# PSU.net
KiCad netlist of a schematic drawn in Altium Designer
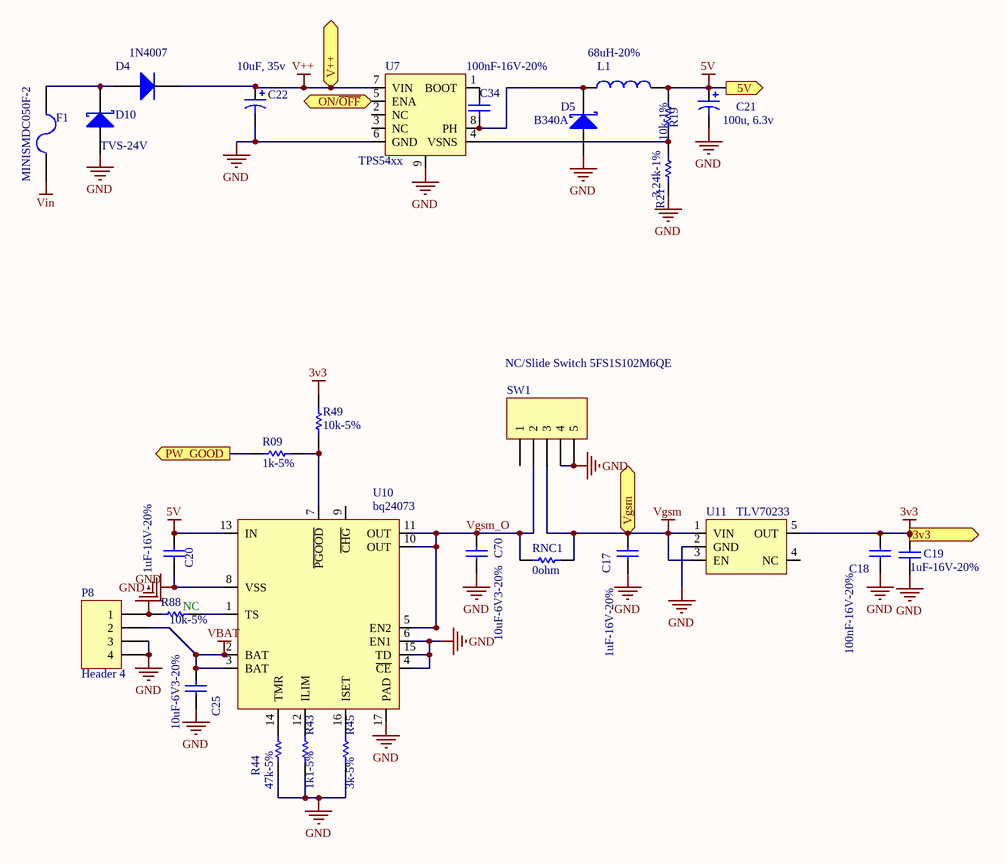
[diagram p0: PSU.SchDoc]

(export (version "E")
  (design (tool "Eeschema 10.0.6"))
  (components
    (comp (ref "C17")
      (value "1uF-16V-20%")
      (footprint "C0603")
      (description "CAP CER 1UF 16V Y5V 0603")
      (fields
        (field (name "MANUFACTURER") "Yageo")
        (field (name "DIGI-KEY PART NUMBER") "311-1372-1-ND")
        (field (name "PUBLISHER") "Altium Limited")
      )
      (libsource (lib "Miscellaneous Devices") (part "Cap"))
    )
    (comp (ref "C18")
      (value "100nF-16V-20%")
      (footprint "C0402")
      (description "CAP CER 0.1UF 16V Y5V 0402")
      (fields
        (field (name "MANUFACTURER") "Yageo")
        (field (name "DIGI-KEY PART NUMBER") "311-1047-1-ND")
        (field (name "PUBLISHER") "Altium Limited")
      )
      (libsource (lib "Miscellaneous Devices") (part "Cap"))
    )
    (comp (ref "C19")
      (value "1uF-16V-20%")
      (footprint "C0603")
      (description "CAP CER 1UF 16V Y5V 0603")
      (fields
        (field (name "MANUFACTURER") "Yageo")
        (field (name "DIGI-KEY PART NUMBER") "311-1372-1-ND")
        (field (name "PUBLISHER") "Altium Limited")
      )
      (libsource (lib "Miscellaneous Devices") (part "Cap"))
    )
    (comp (ref "C20")
      (value "1uF-16V-20%")
      (footprint "C0603")
      (description "CAP CER 1UF 16V Y5V 0603")
      (fields
        (field (name "MANUFACTURER") "Yageo")
        (field (name "DIGI-KEY PART NUMBER") "311-1372-1-ND")
        (field (name "PUBLISHER") "Altium Limited")
      )
      (libsource (lib "Miscellaneous Devices") (part "Cap"))
    )
    (comp (ref "C21")
      (value "100u, 6.3v")
      (footprint "CAPACITOR SIZE_C(D5.3)")
      (description "CAP ALUM 100UF 10V 20% SMD")
      (fields
        (field (name "DIGI-KEY PART NUMBER") "PCE3867TR-ND")
        (field (name "MANUFACTURER") "Panasonic Electronic Components")
        (field (name "PUBLISHER") "Altium Limited")
      )
      (libsource (lib "Miscellaneous Devices") (part "Cap Pol3"))
    )
    (comp (ref "C22")
      (value "10uF, 35v")
      (footprint "CAPACITOR SIZE_C(D5.3)")
      (description "CAP ALUM 10UF 35V 20% SMD")
      (fields
        (field (name "DIGI-KEY PART NUMBER") "PCE3947TR-ND")
        (field (name "MANUFACTURER") "Panasonic Electronic Components")
        (field (name "PUBLISHER") "Altium Limited")
      )
      (libsource (lib "Miscellaneous Devices") (part "Cap Pol3"))
    )
    (comp (ref "C25")
      (value "10uF-6V3-20%")
      (footprint "C0603")
      (description "CAP CER 10UF 6.3V 20% X5R 0603")
      (fields
        (field (name "MANUFACTURER") "Yageo")
        (field (name "DIGI-KEY PART NUMBER") "311-1448-1-ND")
        (field (name "PUBLISHER") "Altium Limited")
      )
      (libsource (lib "Miscellaneous Devices") (part "Cap"))
    )
    (comp (ref "C34")
      (value "100nF-16V-20%")
      (footprint "C0402")
      (description "CAP CER 0.1UF 16V Y5V 0402")
      (fields
        (field (name "MANUFACTURER") "Yageo")
        (field (name "DIGI-KEY PART NUMBER") "311-1047-1-ND")
        (field (name "PUBLISHER") "Altium Limited")
      )
      (libsource (lib "Miscellaneous Devices") (part "Cap"))
    )
    (comp (ref "C70")
      (value "10uF-6V3-20%")
      (footprint "C0603")
      (description "CAP CER 10UF 6.3V 20% X5R 0603")
      (fields
        (field (name "MANUFACTURER") "Yageo")
        (field (name "DIGI-KEY PART NUMBER") "311-1448-1-ND")
        (field (name "PUBLISHER") "Altium Limited")
      )
      (libsource (lib "Miscellaneous Devices") (part "Cap"))
    )
    (comp (ref "D4")
      (value "1N4007")
      (footprint "DO-214AC (SMA)")
      (description "DIODE GEN PURPOSE 1000V 1A SMA")
      (fields
        (field (name "DIGI-KEY PART NUMBER") "641-1018-1-ND")
        (field (name "MANUFACTURER PART NUMBER") "CGRA4007-G")
        (field (name "PUBLISHER") "Altium Limited")
      )
      (libsource (lib "Miscellaneous Devices") (part "Diode"))
    )
    (comp (ref "D5")
      (value "B340A")
      (footprint "DO-214AC (SMA)")
      (description "DIODE SCHOTTKY 40V 3A SMA")
      (fields
        (field (name "DIGI-KEY PART NUMBER") "B340A-E3/61TGITR-ND")
        (field (name "MANUFACTURER PART NUMBER") "B340A-E3/61T")
        (field (name "PUBLISHER") "Altium Limited")
      )
      (libsource (lib "Miscellaneous Devices") (part "D Schottky"))
    )
    (comp (ref "D10")
      (value "TVS-24V")
      (footprint "DO-214AB (SMC)")
      (description "DIODE TVS 24V 1500W UNI 5% SMC")
      (fields
        (field (name "DIGI-KEY PART NUMBER") "SMCJ24ALFTR-ND")
        (field (name "MANUFACTURER PART NUMBER") "SMCJ24A")
        (field (name "PUBLISHER") "Altium Limited")
      )
      (libsource (lib "Miscellaneous Devices") (part "D Schottky"))
    )
    (comp (ref "F1")
      (value "MINISMDC050F-2")
      (footprint "PTC1812")
      (description "POLYSWITCH .50A RESET FUSE SMD")
      (fields
        (field (name "DIGI-KEY PART NUMBER") "MINISMDC050FCT-ND")
        (field (name "MANUFACTURER") "TE Connectivity")
        (field (name "PUBLISHER") "Altium Limited")
      )
      (libsource (lib "Miscellaneous Devices") (part "Fuse 2"))
    )
    (comp (ref "L1")
      (value "68uH-20%")
      (footprint "68uH-1A")
      (description "INDUCTOR POWER 68UH SMD")
      (fields
        (field (name "DIGI-KEY PART NUMBER") "ASPI-6045S-680M-TTR-ND")
        (field (name "MANUFACTURER") "Abracon Corporation")
        (field (name "PUBLISHER") "Altium Limited")
      )
      (libsource (lib "Miscellaneous Devices") (part "Inductor"))
    )
    (comp (ref "P8")
      (value "Header 4")
      (footprint "BAT_CONNECT")
      (description "Header, 4-Pin")
      (fields (field (name "PUBLISHER") "Altium Limited"))
      (libsource (lib "Miscellaneous Connectors") (part "Header 4"))
    )
    (comp (ref "R09")
      (value "1k-5%")
      (footprint "R0402")
      (description "RES 1.0K OHM 1/16W 5% 0402 SMD")
      (fields
        (field (name "DIGI-KEY PART NUMBER") "311-1.0KJRCT-ND")
        (field (name "MANUFACTURER") "Yageo")
        (field (name "PUBLISHER") "Altium Limited")
      )
      (libsource (lib "Miscellaneous Devices") (part "Res1"))
    )
    (comp (ref "R19")
      (value "10k-1%")
      (footprint "R0402")
      (description "RES 10.0K OHM 1/10W 1% 0402 SMD")
      (fields
        (field (name "DIGI-KEY PART NUMBER") "P10.0KLTR-ND")
        (field (name "MANUFACTURER") "Panasonic Electronic Components")
        (field (name "PUBLISHER") "Altium Limited")
      )
      (libsource (lib "Miscellaneous Devices") (part "Res1"))
    )
    (comp (ref "R21")
      (value "3.24k-1%")
      (footprint "R0402")
      (description "RES 3.24K OHM 1/10W 1% 0402 SMD")
      (fields
        (field (name "DIGI-KEY PART NUMBER") "P3.24KLTR-ND")
        (field (name "MANUFACTURER") "Panasonic Electronic Components")
        (field (name "PUBLISHER") "Altium Limited")
      )
      (libsource (lib "Miscellaneous Devices") (part "Res1"))
    )
    (comp (ref "R43")
      (value "1k1-5%")
      (footprint "R0402")
      (description "RES 1.1K OHM 1/16W 5% 0402 SMD")
      (fields
        (field (name "DIGI-KEY PART NUMBER") "311-1.1KJRCT-ND")
        (field (name "MANUFACTURER") "Yageo")
        (field (name "PUBLISHER") "Altium Limited")
      )
      (libsource (lib "Miscellaneous Devices") (part "Res1"))
    )
    (comp (ref "R44")
      (value "47k-5%")
      (footprint "R0402")
      (description "RES 47K OHM 1/16W 5% 0402 SMD")
      (fields
        (field (name "DIGI-KEY PART NUMBER") "311-47KJRCT-ND")
        (field (name "MANUFACTURER") "Yageo")
        (field (name "PUBLISHER") "Altium Limited")
      )
      (libsource (lib "Miscellaneous Devices") (part "Res1"))
    )
    (comp (ref "R45")
      (value "3k-5%")
      (footprint "R0402")
      (description "RES 1.5K OHM 1/16W 5% 0402 SMD")
      (fields
        (field (name "DIGI-KEY PART NUMBER") "311-3.0KJRCT-ND")
        (field (name "MANUFACTURER") "Yageo")
        (field (name "PUBLISHER") "Altium Limited")
      )
      (libsource (lib "Miscellaneous Devices") (part "Res1"))
    )
    (comp (ref "R49")
      (value "10k-5%")
      (footprint "R0402")
      (description "RES 10K OHM 1/16W 5% 0402 SMD")
      (fields
        (field (name "DIGI-KEY PART NUMBER") "311-10KJRCT-ND")
        (field (name "MANUFACTURER") "Yageo")
        (field (name "PUBLISHER") "Altium Limited")
      )
      (libsource (lib "Miscellaneous Devices") (part "Res1"))
    )
    (comp (ref "R88")
      (value "10k-5%")
      (footprint "R0402")
      (description "RES 10K OHM 1/16W 5% 0402 SMD")
      (fields
        (field (name "DIGI-KEY PART NUMBER") "311-10KJRCT-ND")
        (field (name "MANUFACTURER") "Yageo")
        (field (name "PUBLISHER") "Altium Limited")
      )
      (libsource (lib "Miscellaneous Devices") (part "Res1"))
    )
    (comp (ref "RNC1")
      (value "0ohm")
      (footprint "R0402")
      (description "RES 3.24K OHM 1/10W 1% 0402 SMD")
      (fields
        (field (name "DIGI-KEY PART NUMBER") "P3.24KLTR-ND")
        (field (name "MANUFACTURER") "Panasonic Electronic Components")
        (field (name "PUBLISHER") "Altium Limited")
      )
      (libsource (lib "Miscellaneous Devices") (part "Res1"))
    )
    (comp (ref "SW1")
      (value "NC/Slide Switch 5FS1S102M6QE")
      (footprint "SWITCH-PW-AQ")
      (description "Header, 5-Pin")
      (fields (field (name "PUBLISHER") "Altium Limited"))
      (libsource (lib "Miscellaneous Connectors") (part "Header 5"))
    )
    (comp (ref "U7")
      (value "TPS54xx")
      (footprint "HSOIOCN")
      (description "IC REG BUCK ADJ 1A 8SOIC")
      (fields
        (field (name "DIGI-KEY PART NUMBER") "296-26982-2-ND")
        (field (name "MANUFACTURER") "Texas Instruments")
      )
      (libsource (lib "power_ic") (part "TPS54xx"))
    )
    (comp (ref "U10")
      (value "bq24073")
      (footprint "pq24073")
      (description "IC LI-ION CHARGE/PWR MGMT 16-QFN")
      (fields
        (field (name "DIGI-KEY PART NUMBER") "296-23839-1-ND")
        (field (name "MANUFACTURER") "Texas Instruments")
      )
      (libsource (lib "TI_Power") (part "BATTERY_CHARGER"))
    )
    (comp (ref "U11")
      (value "TLV70233")
      (footprint "SOT23-5")
      (description "IC REG LDO 3.3V 0.3A SOT23-5")
      (fields
        (field (name "MANUFACTURER") "Texas Instruments")
        (field (name "DIGI-KEY PART NUMBER") "296-32415-2-ND")
      )
      (libsource (lib "Schlib1") (part "XC6209B332MRN_SOT-25"))
    )
  )
  (nets
    (net (code "2") (name "/ON{slash}~{OFF}") (class "Default")
      (node (ref "U7") (pin "5") (pinfunction "ENA_5") (pintype "passive"))
    )
    (net (code "3") (name "/PW_GOOD") (class "Default")
      (node (ref "R09") (pin "2") (pinfunction "2_2") (pintype "passive"))
    )
    (net (code "4") (name "/Vgsm_O") (class "Default")
      (node (ref "C70") (pin "2") (pinfunction "2_2") (pintype "passive"))
      (node (ref "RNC1") (pin "2") (pinfunction "2_2") (pintype "passive"))
      (node (ref "SW1") (pin "2") (pinfunction "2_2") (pintype "passive"))
      (node (ref "U10") (pin "10") (pinfunction "OUT_10") (pintype "passive"))
      (node (ref "U10") (pin "11") (pinfunction "OUT_11") (pintype "passive"))
      (node (ref "U10") (pin "5") (pinfunction "EN2_5") (pintype "passive"))
    )
    (net (code "5") (name "3v3") (class "Default")
      (node (ref "C18") (pin "2") (pinfunction "2_2") (pintype "passive"))
      (node (ref "C19") (pin "1") (pinfunction "1_1") (pintype "passive"))
      (node (ref "R49") (pin "2") (pinfunction "2_2") (pintype "passive"))
      (node (ref "U11") (pin "5") (pinfunction "OUT_5") (pintype "passive"))
    )
    (net (code "6") (name "5V") (class "Default")
      (node (ref "C20") (pin "2") (pinfunction "2_2") (pintype "passive"))
      (node (ref "C21") (pin "1") (pinfunction "1_1") (pintype "passive"))
      (node (ref "L1") (pin "2") (pinfunction "2_2") (pintype "passive"))
      (node (ref "R19") (pin "1") (pinfunction "1_1") (pintype "passive"))
      (node (ref "U10") (pin "13") (pinfunction "IN_13") (pintype "passive"))
    )
    (net (code "7") (name "GND") (class "Default")
      (node (ref "C17") (pin "2") (pinfunction "2_2") (pintype "passive"))
      (node (ref "C18") (pin "1") (pinfunction "1_1") (pintype "passive"))
      (node (ref "C19") (pin "2") (pinfunction "2_2") (pintype "passive"))
      (node (ref "C20") (pin "1") (pinfunction "1_1") (pintype "passive"))
      (node (ref "C21") (pin "2") (pinfunction "2_2") (pintype "passive"))
      (node (ref "C22") (pin "2") (pinfunction "2_2") (pintype "passive"))
      (node (ref "C25") (pin "1") (pinfunction "1_1") (pintype "passive"))
      (node (ref "C70") (pin "1") (pinfunction "1_1") (pintype "passive"))
      (node (ref "D10") (pin "1") (pinfunction "A_1") (pintype "passive"))
      (node (ref "D5") (pin "1") (pinfunction "A_1") (pintype "passive"))
      (node (ref "P8") (pin "1") (pinfunction "1_1") (pintype "passive"))
      (node (ref "P8") (pin "3") (pinfunction "3_3") (pintype "passive"))
      (node (ref "P8") (pin "4") (pinfunction "4_4") (pintype "passive"))
      (node (ref "R21") (pin "1") (pinfunction "1_1") (pintype "passive"))
      (node (ref "R43") (pin "2") (pinfunction "2_2") (pintype "passive"))
      (node (ref "R44") (pin "2") (pinfunction "2_2") (pintype "passive"))
      (node (ref "R45") (pin "2") (pinfunction "2_2") (pintype "passive"))
      (node (ref "R88") (pin "2") (pinfunction "2_2") (pintype "passive"))
      (node (ref "SW1") (pin "4") (pinfunction "4_4") (pintype "passive"))
      (node (ref "SW1") (pin "5") (pinfunction "5_5") (pintype "passive"))
      (node (ref "U10") (pin "15") (pinfunction "TD_15") (pintype "passive"))
      (node (ref "U10") (pin "17") (pinfunction "PAD_17") (pintype "passive"))
      (node (ref "U10") (pin "4") (pinfunction "~{CE}_4") (pintype "passive"))
      (node (ref "U10") (pin "6") (pinfunction "EN1_6") (pintype "passive"))
      (node (ref "U10") (pin "8") (pinfunction "VSS_8") (pintype "passive"))
      (node (ref "U11") (pin "2") (pinfunction "GND_2") (pintype "passive"))
      (node (ref "U7") (pin "6") (pinfunction "GND_6") (pintype "passive"))
      (node (ref "U7") (pin "9") (pinfunction "G-PAD_9") (pintype "passive"))
    )
    (net (code "8") (name "Net-(D5-K)") (class "Default")
      (node (ref "C34") (pin "2") (pinfunction "2_2") (pintype "passive"))
      (node (ref "D5") (pin "2") (pinfunction "K_2") (pintype "passive"))
      (node (ref "L1") (pin "1") (pinfunction "1_1") (pintype "passive"))
      (node (ref "U7") (pin "8") (pinfunction "PH_8") (pintype "passive"))
    )
    (net (code "9") (name "Net-(D10-K)") (class "Default")
      (node (ref "D10") (pin "2") (pinfunction "K_2") (pintype "passive"))
      (node (ref "D4") (pin "1") (pinfunction "A_1") (pintype "passive"))
      (node (ref "F1") (pin "2") (pinfunction "2_2") (pintype "passive"))
    )
    (net (code "10") (name "Net-(U7-BOOT)") (class "Default")
      (node (ref "C34") (pin "1") (pinfunction "1_1") (pintype "passive"))
      (node (ref "U7") (pin "1") (pinfunction "BOOT_1") (pintype "passive"))
    )
    (net (code "11") (name "Net-(U7-VSNS)") (class "Default")
      (node (ref "R19") (pin "2") (pinfunction "2_2") (pintype "passive"))
      (node (ref "R21") (pin "2") (pinfunction "2_2") (pintype "passive"))
      (node (ref "U7") (pin "4") (pinfunction "VSNS_4") (pintype "passive"))
    )
    (net (code "12") (name "Net-(U10-ILIM)") (class "Default")
      (node (ref "R43") (pin "1") (pinfunction "1_1") (pintype "passive"))
      (node (ref "U10") (pin "12") (pinfunction "ILIM_12") (pintype "passive"))
    )
    (net (code "13") (name "Net-(U10-ISET)") (class "Default")
      (node (ref "R45") (pin "1") (pinfunction "1_1") (pintype "passive"))
      (node (ref "U10") (pin "16") (pinfunction "ISET_16") (pintype "passive"))
    )
    (net (code "14") (name "Net-(U10-TMR)") (class "Default")
      (node (ref "R44") (pin "1") (pinfunction "1_1") (pintype "passive"))
      (node (ref "U10") (pin "14") (pinfunction "TMR_14") (pintype "passive"))
    )
    (net (code "15") (name "Net-(U10-TS)") (class "Default")
      (node (ref "R88") (pin "1") (pinfunction "1_1") (pintype "passive"))
      (node (ref "U10") (pin "1") (pinfunction "TS_1") (pintype "passive"))
    )
    (net (code "16") (name "Net-(U10-~{PGOOD})") (class "Default")
      (node (ref "R09") (pin "1") (pinfunction "1_1") (pintype "passive"))
      (node (ref "R49") (pin "1") (pinfunction "1_1") (pintype "passive"))
      (node (ref "U10") (pin "7") (pinfunction "~{PGOOD}_7") (pintype "passive"))
    )
    (net (code "17") (name "V++") (class "Default")
      (node (ref "C22") (pin "1") (pinfunction "1_1") (pintype "passive"))
      (node (ref "D4") (pin "2") (pinfunction "K_2") (pintype "passive"))
      (node (ref "U7") (pin "7") (pinfunction "VIN_7") (pintype "passive"))
    )
    (net (code "18") (name "VBAT") (class "Default")
      (node (ref "C25") (pin "2") (pinfunction "2_2") (pintype "passive"))
      (node (ref "P8") (pin "2") (pinfunction "2_2") (pintype "passive"))
      (node (ref "U10") (pin "2") (pinfunction "BAT_2") (pintype "passive"))
      (node (ref "U10") (pin "3") (pinfunction "BAT_3") (pintype "passive"))
    )
    (net (code "19") (name "Vgsm") (class "Default")
      (node (ref "C17") (pin "1") (pinfunction "1_1") (pintype "passive"))
      (node (ref "RNC1") (pin "1") (pinfunction "1_1") (pintype "passive"))
      (node (ref "SW1") (pin "3") (pinfunction "3_3") (pintype "passive"))
      (node (ref "U11") (pin "1") (pinfunction "VIN_1") (pintype "passive"))
      (node (ref "U11") (pin "3") (pinfunction "EN_3") (pintype "passive"))
    )
    (net (code "20") (name "Vin") (class "Default")
      (node (ref "F1") (pin "1") (pinfunction "1_1") (pintype "passive"))
    )
    (net (code "21") (name "unconnected-(SW1-Pad1)") (class "Default")
      (node (ref "SW1") (pin "1") (pinfunction "1_1") (pintype "passive"))
    )
    (net (code "22") (name "unconnected-(U7-NC-Pad2)") (class "Default")
      (node (ref "U7") (pin "2") (pinfunction "NC_2") (pintype "passive"))
    )
    (net (code "23") (name "unconnected-(U7-NC-Pad3)") (class "Default")
      (node (ref "U7") (pin "3") (pinfunction "NC_3") (pintype "passive"))
    )
    (net (code "24") (name "unconnected-(U10-~{CHG}-Pad9)") (class "Default")
      (node (ref "U10") (pin "9") (pinfunction "~{CHG}_9") (pintype "passive"))
    )
    (net (code "25") (name "unconnected-(U11-NC-Pad4)") (class "Default")
      (node (ref "U11") (pin "4") (pinfunction "NC_4") (pintype "passive"))
    )
  )
)
